# RelayDriver.net
KiCad netlist of a schematic drawn in Altium Designer
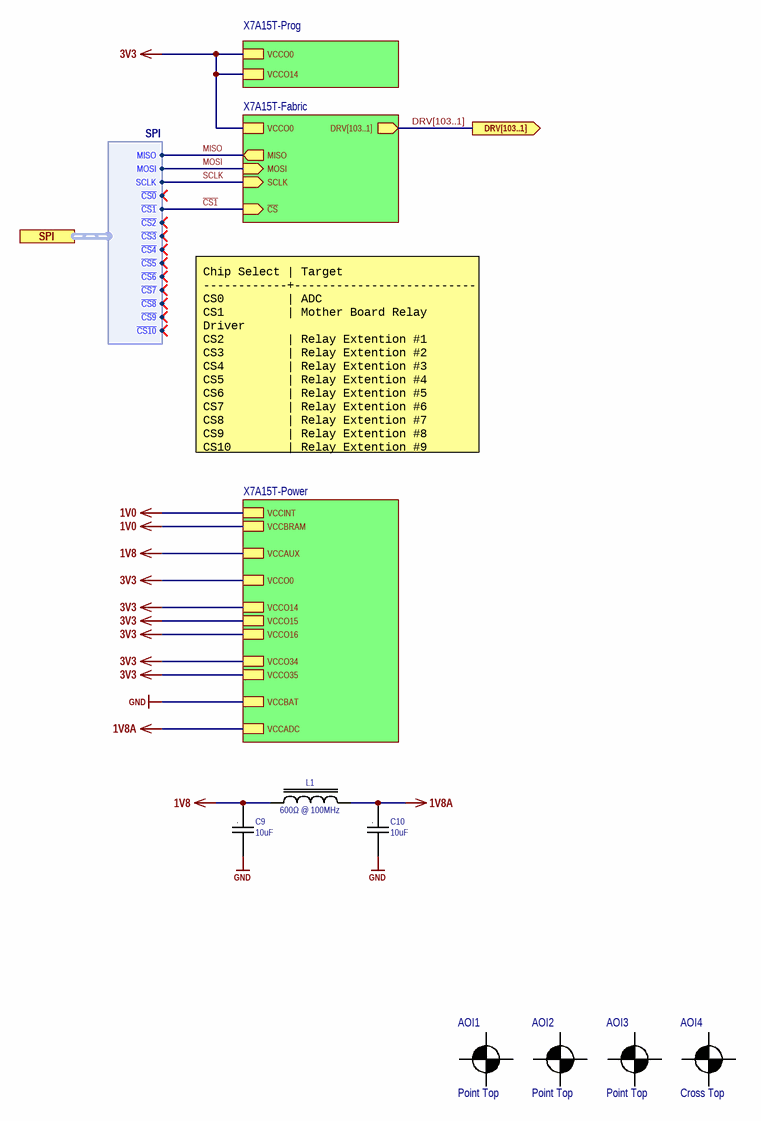
[diagram p0: RelayDriver.SchDoc]

(export (version "E")
  (design (tool "Eeschema 10.0.6"))
  (components
    (comp (ref "AOI1")
      (value "AOI")
      (footprint "Fiducial Point")
      (description "Assembly AOI")
      (fields (field (name "SHAPE") "Point Top") (field (name "13. CREATED DATE/NAME") "AUG2018/Hören"))
      (libsource (lib "PCB-Tester-Board-V1") (part "Fiducial"))
    )
    (comp (ref "AOI2")
      (value "AOI")
      (footprint "Fiducial Point")
      (description "Assembly AOI")
      (fields (field (name "SHAPE") "Point Top") (field (name "13. CREATED DATE/NAME") "AUG2018/Hören"))
      (libsource (lib "PCB-Tester-Board-V1") (part "Fiducial"))
    )
    (comp (ref "AOI3")
      (value "AOI")
      (footprint "Fiducial Point")
      (description "Assembly AOI")
      (fields (field (name "SHAPE") "Point Top") (field (name "13. CREATED DATE/NAME") "AUG2018/Hören"))
      (libsource (lib "PCB-Tester-Board-V1") (part "Fiducial"))
    )
    (comp (ref "AOI4")
      (value "AOI")
      (footprint "Fiducial Cross")
      (description "Assembly AOI")
      (fields (field (name "SHAPE") "Cross Top") (field (name "13. CREATED DATE/NAME") "AUG2018/Hören"))
      (libsource (lib "PCB-Tester-Board-V1") (part "Fiducial"))
    )
    (comp (ref "C9")
      (value "10uF")
      (footprint "C0805 Reflow")
      (description "CAP CER 10UF 10V X7R 0805")
      (fields
        (field (name "TOLERANCE") "±10%")
        (field (name "02. DISTRIBUTOR PART NUMBER") "1276-1764-6-ND")
        (field (name "13. CREATED DATE/NAME") "AUG2018/Hören")
      )
      (libsource (lib "chickenfood") (part "C"))
    )
    (comp (ref "C10")
      (value "10uF")
      (footprint "C0805 Reflow")
      (description "CAP CER 10UF 10V X7R 0805")
      (fields
        (field (name "TOLERANCE") "±10%")
        (field (name "02. DISTRIBUTOR PART NUMBER") "1276-1764-6-ND")
        (field (name "13. CREATED DATE/NAME") "AUG2018/Hören")
      )
      (libsource (lib "chickenfood") (part "C"))
    )
    (comp (ref "L1")
      (value "L")
      (footprint "FB0805")
      (description "FERRITE BEAD 600 OHM 0805 1LN")
      (fields
        (field (name "NOMINAL IMPEDANCE") "600Ω @ 100MHz")
        (field (name "02. DISTRIBUTOR PART NUMBER") "732-1620-6-ND")
        (field (name "07. MANUFACTURER  PART NUMBER") "742792040")
        (field (name "13. CREATED DATE/NAME") "AUG2018/Hören")
      )
      (libsource (lib "chickenfood") (part "FB"))
    )
  )
  (nets
    (net (code "112") (name "1V8") (class "Default")
      (node (ref "C9") (pin "1") (pinfunction "1_1") (pintype "passive"))
      (node (ref "L1") (pin "1") (pinfunction "1_1") (pintype "passive"))
    )
    (net (code "113") (name "1V8A") (class "Default")
      (node (ref "C10") (pin "1") (pinfunction "1_1") (pintype "passive"))
      (node (ref "L1") (pin "2") (pinfunction "2_2") (pintype "passive"))
    )
    (net (code "115") (name "GND") (class "Default")
      (node (ref "C10") (pin "2") (pinfunction "2_2") (pintype "passive"))
      (node (ref "C9") (pin "2") (pinfunction "2_2") (pintype "passive"))
    )
  )
)
